# tentprotector-tht.net
KiCad netlist of a schematic drawn in EAGLE
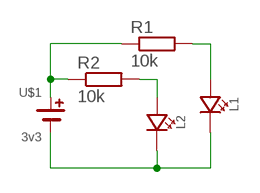
[diagram p0: schematic, sheet 1]

(export (version "E")
  (design (tool "Eeschema 10.0.6"))
  (components
    (comp (ref "L1")
      (value "LED5MM")
      (footprint "eagle-import:LED-5MM")
      (libsource (lib "eagle-import") (part "LED5MM"))
    )
    (comp (ref "L2")
      (value "LED5MM")
      (footprint "eagle-import:LED-5MM")
      (libsource (lib "eagle-import") (part "LED5MM"))
    )
    (comp (ref "R1")
      (value "10k")
      (footprint "eagle-import:0207_7")
      (libsource (lib "eagle-import") (part "R-EU_0207/7"))
    )
    (comp (ref "R2")
      (value "10k")
      (footprint "eagle-import:0207_7")
      (libsource (lib "eagle-import") (part "R-EU_0207/7"))
    )
    (comp (ref "U$1")
      (value "3v3")
      (footprint "eagle-import:BATTERY-CR2030-MIN")
      (libsource (lib "eagle-import") (part "BATTERY2032-MIN"))
    )
  )
  (nets
    (net (code "1") (name "Net-(L1-C)") (class "Default")
      (node (ref "L1") (pin "K") (pinfunction "C_K") (pintype "bidirectional"))
      (node (ref "L2") (pin "K") (pinfunction "C_K") (pintype "bidirectional"))
      (node (ref "U$1") (pin "N$1") (pinfunction "MINUS_N$1") (pintype "bidirectional"))
    )
    (net (code "2") (name "Net-(L1-PadA)") (class "Default")
      (node (ref "L1") (pin "A") (pinfunction "A_A") (pintype "bidirectional"))
      (node (ref "R1") (pin "2") (pinfunction "2_2") (pintype "passive"))
    )
    (net (code "3") (name "Net-(L2-PadA)") (class "Default")
      (node (ref "L2") (pin "A") (pinfunction "A_A") (pintype "bidirectional"))
      (node (ref "R2") (pin "2") (pinfunction "2_2") (pintype "passive"))
    )
    (net (code "4") (name "Net-(R1-Pad1)") (class "Default")
      (node (ref "R1") (pin "1") (pinfunction "1_1") (pintype "passive"))
      (node (ref "R2") (pin "1") (pinfunction "1_1") (pintype "passive"))
      (node (ref "U$1") (pin "P$1") (pinfunction "PLUS_P$1") (pintype "bidirectional"))
      (node (ref "U$1") (pin "P$2") (pinfunction "PLUS_P$2") (pintype "bidirectional"))
    )
  )
)
